# mach_sac_acquy.net
KiCad netlist of a schematic drawn in Altium Designer
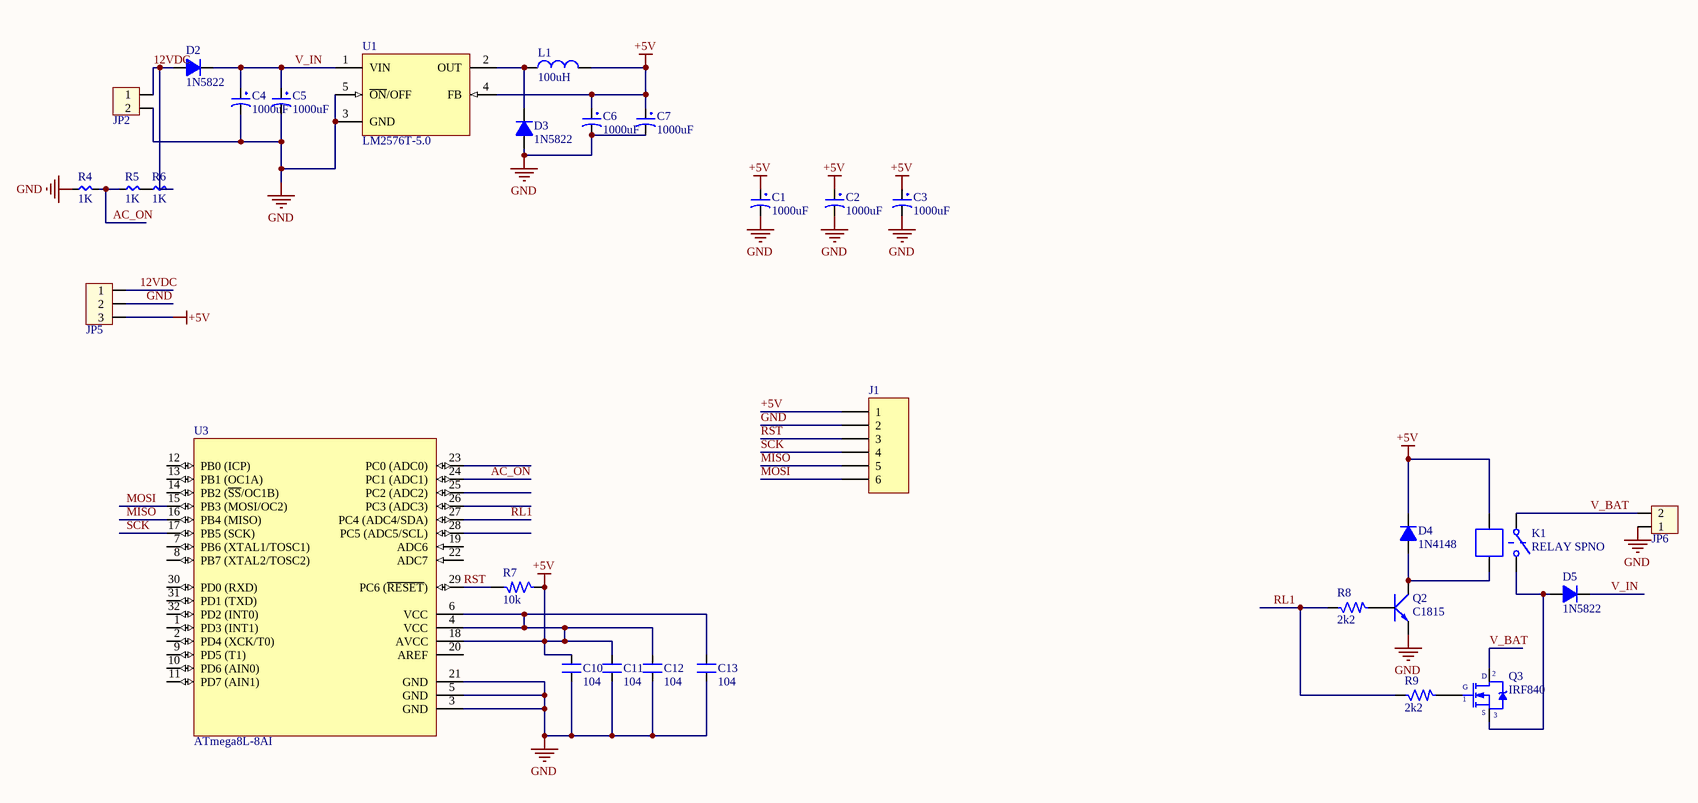
[diagram p0: mach_sac_acquy.SchDoc]

(export (version "E")
  (design (tool "Eeschema 10.0.6"))
  (components
    (comp (ref "C1")
      (value "1000uF")
      (footprint "CP1/2")
      (description "C 47uF/50V , 220uF/16V")
      (libsource (lib "Luyen_Schematics") (part "CP2"))
    )
    (comp (ref "C2")
      (value "1000uF")
      (footprint "CP1/2")
      (description "C 47uF/50V , 220uF/16V")
      (libsource (lib "Luyen_Schematics") (part "CP2"))
    )
    (comp (ref "C3")
      (value "1000uF")
      (footprint "CP1/2")
      (description "C 47uF/50V , 220uF/16V")
      (libsource (lib "Luyen_Schematics") (part "CP2"))
    )
    (comp (ref "C4")
      (value "1000uF")
      (footprint "CP2/4")
      (description "C 47uF/50V , 220uF/16V")
      (libsource (lib "Luyen_Schematics") (part "CP2"))
    )
    (comp (ref "C5")
      (value "1000uF")
      (footprint "CP2/4")
      (description "C 47uF/50V , 220uF/16V")
      (libsource (lib "Luyen_Schematics") (part "CP2"))
    )
    (comp (ref "C6")
      (value "1000uF")
      (footprint "CP2/4")
      (description "C 47uF/50V , 220uF/16V")
      (libsource (lib "Luyen_Schematics") (part "CP2"))
    )
    (comp (ref "C7")
      (value "1000uF")
      (footprint "CP2/4")
      (description "C 47uF/50V , 220uF/16V")
      (libsource (lib "Luyen_Schematics") (part "CP2"))
    )
    (comp (ref "C10")
      (value "104")
      (footprint "SM-0805")
      (description "Cap SMD")
      (libsource (lib "Luyen_Schematics") (part "CM"))
    )
    (comp (ref "C11")
      (value "104")
      (footprint "SM-0805")
      (description "Cap SMD")
      (libsource (lib "Luyen_Schematics") (part "CM"))
    )
    (comp (ref "C12")
      (value "104")
      (footprint "SM-0805")
      (description "Cap SMD")
      (libsource (lib "Luyen_Schematics") (part "CM"))
    )
    (comp (ref "C13")
      (value "104")
      (footprint "SM-0805")
      (description "Cap SMD")
      (libsource (lib "Luyen_Schematics") (part "CM"))
    )
    (comp (ref "D2")
      (value "1N5822")
      (footprint "D5A")
      (description "Diode 5A")
      (libsource (lib "Luyen_Schematics") (part "D5A"))
    )
    (comp (ref "D3")
      (value "1N5822")
      (footprint "D5A")
      (description "Diode 5A")
      (libsource (lib "Luyen_Schematics") (part "D5A"))
    )
    (comp (ref "D4")
      (value "1N4148")
      (footprint "1n4148 smd")
      (description "Diode 1A")
      (libsource (lib "Luyen_Schematics") (part "D1A"))
    )
    (comp (ref "D5")
      (value "1N5822")
      (footprint "D5A")
      (description "Diode 5A")
      (libsource (lib "Luyen_Schematics") (part "D5A"))
    )
    (comp (ref "J1")
      (value "Connector 5")
      (footprint "HDR1X6")
      (description "Header, 6-Pin")
      (fields (field (name "PUBLISHER") "Altium Limited"))
      (libsource (lib "Luyen_Schematics") (part "Header 6"))
    )
    (comp (ref "JP2")
      (value "Connector 2")
      (footprint "CON2")
      (libsource (lib "Luyen_Schematics") (part "CON2"))
    )
    (comp (ref "JP5")
      (value "Connector 3")
      (footprint "CON3")
      (libsource (lib "Luyen_Schematics") (part "CON3"))
    )
    (comp (ref "JP6") (value "Connector 2") (footprint "CON2") (libsource (lib "") (part "CON2_1")))
    (comp (ref "K1")
      (value "RELAY SPNO")
      (footprint "RELAY SONGCHUAN 834")
      (description "SINGLE Pole Dual-Throw Relay")
      (fields (field (name "PUBLISHER") "Altium Limited"))
      (libsource (lib "Luyen_Schematics") (part "RELAY SPNO"))
    )
    (comp (ref "L1")
      (value "100uH")
      (footprint "Inductor200")
      (description "Inductor")
      (libsource (lib "Luyen_Schematics") (part "Inductor"))
    )
    (comp (ref "Q2")
      (value "C1815")
      (footprint "SOT23B")
      (description "NPN 600mW, ECB")
      (libsource (lib "Luyen_Schematics") (part "C1815"))
    )
    (comp (ref "Q3")
      (value "IRF840")
      (footprint "QTO-220")
      (description "MOSFET N - CHANNEL 500V - 0.75 - 8A - TO-220")
      (libsource (lib "Luyen_Schematics") (part "IRF840"))
    )
    (comp (ref "R4")
      (value "1K")
      (footprint "SM-0805")
      (description "Resistor")
      (libsource (lib "THU VIEN CHAN") (part "RES 0805 BUT"))
    )
    (comp (ref "R5")
      (value "1K")
      (footprint "SM-0805")
      (description "Resistor")
      (libsource (lib "THU VIEN CHAN") (part "RES 0805 BUT"))
    )
    (comp (ref "R6")
      (value "1K")
      (footprint "SM-0805")
      (description "Resistor")
      (libsource (lib "THU VIEN CHAN") (part "RES 0805 BUT"))
    )
    (comp (ref "R7")
      (value "10k")
      (description "Resistor 1/4W")
      (libsource (lib "Luyen_Schematics") (part "R"))
    )
    (comp (ref "R8")
      (value "2k2")
      (description "Resistor 1/4W")
      (libsource (lib "Luyen_Schematics") (part "R"))
    )
    (comp (ref "R9")
      (value "2k2")
      (description "Resistor 1/4W")
      (libsource (lib "Luyen_Schematics") (part "R"))
    )
    (comp (ref "U1")
      (value "LM2576T-5.0")
      (description "SIMPLE SWITCHER; 3A Step-Down Voltage Regulator")
      (fields
        (field (name "MANUFACTURER") "National Semiconductor")
        (field (name "DIGIKEYPARTNUMBER") "LM2576T-5.0-ND")
        (field (name "PUBLISHER") "Altium Limited")
      )
      (libsource (lib "Luyen_Schematics") (part "LM2576T-5.0"))
    )
    (comp (ref "U3")
      (value "ATmega8L-8AI")
      (footprint "QFP7X7-G32/X.45N")
      (description "8-Bit AVR Microcontroller with 8K Bytes of In-System Programmable Flash Memory")
      (fields (field (name "PUBLISHER") "Altium Limited"))
      (libsource (lib "Atmel Microcontroller 8-Bit AVR") (part "ATmega8L-8AI"))
    )
  )
  (nets
    (net (code "1") (name "+5V") (class "Default")
      (node (ref "C1") (pin "1") (pinfunction "1_1") (pintype "passive"))
      (node (ref "C10") (pin "2") (pinfunction "2_2") (pintype "passive"))
      (node (ref "C11") (pin "2") (pinfunction "2_2") (pintype "passive"))
      (node (ref "C12") (pin "2") (pinfunction "2_2") (pintype "passive"))
      (node (ref "C13") (pin "2") (pinfunction "2_2") (pintype "passive"))
      (node (ref "C2") (pin "1") (pinfunction "1_1") (pintype "passive"))
      (node (ref "C3") (pin "1") (pinfunction "1_1") (pintype "passive"))
      (node (ref "C6") (pin "1") (pinfunction "1_1") (pintype "passive"))
      (node (ref "C7") (pin "1") (pinfunction "1_1") (pintype "passive"))
      (node (ref "D4") (pin "2") (pinfunction "K_2") (pintype "passive"))
      (node (ref "J1") (pin "1") (pinfunction "1_1") (pintype "passive"))
      (node (ref "JP5") (pin "3") (pinfunction "3_3") (pintype "passive"))
      (node (ref "K1") (pin "1") (pinfunction "1_1") (pintype "passive"))
      (node (ref "L1") (pin "2") (pinfunction "2_2") (pintype "passive"))
      (node (ref "R7") (pin "1") (pinfunction "1_1") (pintype "passive"))
      (node (ref "U1") (pin "4") (pinfunction "FB_4") (pintype "input"))
      (node (ref "U3") (pin "18") (pinfunction "AVCC_18") (pintype "power_in"))
      (node (ref "U3") (pin "4") (pinfunction "VCC_4") (pintype "power_in"))
      (node (ref "U3") (pin "6") (pinfunction "VCC_6") (pintype "power_in"))
    )
    (net (code "2") (name "/12VDC") (class "Default")
      (node (ref "D2") (pin "1") (pinfunction "A_1") (pintype "passive"))
      (node (ref "JP2") (pin "1") (pinfunction "1_1") (pintype "passive"))
      (node (ref "JP5") (pin "1") (pinfunction "1_1") (pintype "passive"))
      (node (ref "R6") (pin "1") (pinfunction "1_1") (pintype "passive"))
    )
    (net (code "3") (name "/AC_ON") (class "Default")
      (node (ref "R4") (pin "1") (pinfunction "1_1") (pintype "passive"))
      (node (ref "R5") (pin "2") (pinfunction "2_2") (pintype "passive"))
      (node (ref "U3") (pin "24") (pinfunction "PC1_(ADC1)_24") (pintype "bidirectional"))
    )
    (net (code "4") (name "/MISO") (class "Default")
      (node (ref "J1") (pin "5") (pinfunction "5_5") (pintype "passive"))
      (node (ref "U3") (pin "16") (pinfunction "PB4_(MISO)_16") (pintype "bidirectional"))
    )
    (net (code "5") (name "/MOSI") (class "Default")
      (node (ref "J1") (pin "6") (pinfunction "6_6") (pintype "passive"))
      (node (ref "U3") (pin "15") (pinfunction "PB3_(MOSI/OC2)_15") (pintype "bidirectional"))
    )
    (net (code "6") (name "/RL1") (class "Default")
      (node (ref "R8") (pin "1") (pinfunction "1_1") (pintype "passive"))
      (node (ref "R9") (pin "1") (pinfunction "1_1") (pintype "passive"))
      (node (ref "U3") (pin "27") (pinfunction "PC4_(ADC4/SDA)_27") (pintype "bidirectional"))
    )
    (net (code "7") (name "/RST") (class "Default")
      (node (ref "J1") (pin "3") (pinfunction "3_3") (pintype "passive"))
      (node (ref "R7") (pin "2") (pinfunction "2_2") (pintype "passive"))
      (node (ref "U3") (pin "29") (pinfunction "PC6_(~{RESET})_29") (pintype "bidirectional"))
    )
    (net (code "8") (name "/SCK") (class "Default")
      (node (ref "J1") (pin "4") (pinfunction "4_4") (pintype "passive"))
      (node (ref "U3") (pin "17") (pinfunction "PB5_(SCK)_17") (pintype "bidirectional"))
    )
    (net (code "9") (name "/V_BAT") (class "Default")
      (node (ref "JP6") (pin "2") (pinfunction "2_2") (pintype "passive"))
      (node (ref "K1") (pin "4") (pinfunction "4_4") (pintype "passive"))
      (node (ref "Q3") (pin "2") (pinfunction "D_2") (pintype "passive"))
    )
    (net (code "10") (name "/V_IN") (class "Default")
      (node (ref "C4") (pin "1") (pinfunction "1_1") (pintype "passive"))
      (node (ref "C5") (pin "1") (pinfunction "1_1") (pintype "passive"))
      (node (ref "D2") (pin "2") (pinfunction "K_2") (pintype "passive"))
      (node (ref "D5") (pin "2") (pinfunction "K_2") (pintype "passive"))
      (node (ref "U1") (pin "1") (pinfunction "VIN_1") (pintype "power_in"))
    )
    (net (code "11") (name "GND") (class "Default")
      (node (ref "C1") (pin "2") (pinfunction "2_2") (pintype "passive"))
      (node (ref "C10") (pin "1") (pinfunction "1_1") (pintype "passive"))
      (node (ref "C11") (pin "1") (pinfunction "1_1") (pintype "passive"))
      (node (ref "C12") (pin "1") (pinfunction "1_1") (pintype "passive"))
      (node (ref "C13") (pin "1") (pinfunction "1_1") (pintype "passive"))
      (node (ref "C2") (pin "2") (pinfunction "2_2") (pintype "passive"))
      (node (ref "C3") (pin "2") (pinfunction "2_2") (pintype "passive"))
      (node (ref "C4") (pin "2") (pinfunction "2_2") (pintype "passive"))
      (node (ref "C5") (pin "2") (pinfunction "2_2") (pintype "passive"))
      (node (ref "C6") (pin "2") (pinfunction "2_2") (pintype "passive"))
      (node (ref "C7") (pin "2") (pinfunction "2_2") (pintype "passive"))
      (node (ref "D3") (pin "1") (pinfunction "A_1") (pintype "passive"))
      (node (ref "J1") (pin "2") (pinfunction "2_2") (pintype "passive"))
      (node (ref "JP2") (pin "2") (pinfunction "2_2") (pintype "passive"))
      (node (ref "JP5") (pin "2") (pinfunction "2_2") (pintype "passive"))
      (node (ref "JP6") (pin "1") (pinfunction "1_1") (pintype "passive"))
      (node (ref "Q2") (pin "1") (pinfunction "E_1") (pintype "passive"))
      (node (ref "R4") (pin "2") (pinfunction "2_2") (pintype "passive"))
      (node (ref "U1") (pin "3") (pinfunction "GND_3") (pintype "power_in"))
      (node (ref "U1") (pin "5") (pinfunction "~{ON}/OFF_5") (pintype "input"))
      (node (ref "U3") (pin "21") (pinfunction "GND_21") (pintype "power_in"))
      (node (ref "U3") (pin "3") (pinfunction "GND_3") (pintype "power_in"))
      (node (ref "U3") (pin "5") (pinfunction "GND_5") (pintype "power_in"))
    )
    (net (code "12") (name "Net-(D3-K)") (class "Default")
      (node (ref "D3") (pin "2") (pinfunction "K_2") (pintype "passive"))
      (node (ref "L1") (pin "1") (pinfunction "1_1") (pintype "passive"))
      (node (ref "U1") (pin "2") (pinfunction "OUT_2") (pintype "power_in"))
    )
    (net (code "13") (name "Net-(D4-A)") (class "Default")
      (node (ref "D4") (pin "1") (pinfunction "A_1") (pintype "passive"))
      (node (ref "K1") (pin "2") (pinfunction "2_2") (pintype "passive"))
      (node (ref "Q2") (pin "2") (pinfunction "C_2") (pintype "passive"))
    )
    (net (code "14") (name "Net-(D5-A)") (class "Default")
      (node (ref "D5") (pin "1") (pinfunction "A_1") (pintype "passive"))
      (node (ref "K1") (pin "3") (pinfunction "3_3") (pintype "passive"))
      (node (ref "Q3") (pin "3") (pinfunction "S_3") (pintype "passive"))
    )
    (net (code "15") (name "Net-(Q2-B)") (class "Default")
      (node (ref "Q2") (pin "3") (pinfunction "B_3") (pintype "passive"))
      (node (ref "R8") (pin "2") (pinfunction "2_2") (pintype "passive"))
    )
    (net (code "16") (name "Net-(Q3-G)") (class "Default")
      (node (ref "Q3") (pin "1") (pinfunction "G_1") (pintype "passive"))
      (node (ref "R9") (pin "2") (pinfunction "2_2") (pintype "passive"))
    )
    (net (code "17") (name "Net-(R5-Pad1)") (class "Default")
      (node (ref "R5") (pin "1") (pinfunction "1_1") (pintype "passive"))
      (node (ref "R6") (pin "2") (pinfunction "2_2") (pintype "passive"))
    )
    (net (code "18") (name "unconnected-(U3-ADC6-Pad19)") (class "Default")
      (node (ref "U3") (pin "19") (pinfunction "ADC6_19") (pintype "input"))
    )
    (net (code "19") (name "unconnected-(U3-ADC7-Pad22)") (class "Default")
      (node (ref "U3") (pin "22") (pinfunction "ADC7_22") (pintype "input"))
    )
    (net (code "20") (name "unconnected-(U3-AREF-Pad20)") (class "Default")
      (node (ref "U3") (pin "20") (pinfunction "AREF_20") (pintype "passive"))
    )
    (net (code "21") (name "unconnected-(U3-PB0_(ICP)-Pad12)") (class "Default")
      (node (ref "U3") (pin "12") (pinfunction "PB0_(ICP)_12") (pintype "bidirectional"))
    )
    (net (code "22") (name "unconnected-(U3-PB1_(OC1A)-Pad13)") (class "Default")
      (node (ref "U3") (pin "13") (pinfunction "PB1_(OC1A)_13") (pintype "bidirectional"))
    )
    (net (code "23") (name "unconnected-(U3-PB2_(~{SS}{slash}OC1B)-Pad14)") (class "Default")
      (node (ref "U3") (pin "14") (pinfunction "PB2_(~{SS}/OC1B)_14") (pintype "bidirectional"))
    )
    (net (code "24") (name "unconnected-(U3-PB6_(XTAL1{slash}TOSC1)-Pad7)") (class "Default")
      (node (ref "U3") (pin "7") (pinfunction "PB6_(XTAL1/TOSC1)_7") (pintype "bidirectional"))
    )
    (net (code "25") (name "unconnected-(U3-PB7_(XTAL2{slash}TOSC2)-Pad8)") (class "Default")
      (node (ref "U3") (pin "8") (pinfunction "PB7_(XTAL2/TOSC2)_8") (pintype "bidirectional"))
    )
    (net (code "26") (name "unconnected-(U3-PC0_(ADC0)-Pad23)") (class "Default")
      (node (ref "U3") (pin "23") (pinfunction "PC0_(ADC0)_23") (pintype "bidirectional"))
    )
    (net (code "27") (name "unconnected-(U3-PC2_(ADC2)-Pad25)") (class "Default")
      (node (ref "U3") (pin "25") (pinfunction "PC2_(ADC2)_25") (pintype "bidirectional"))
    )
    (net (code "28") (name "unconnected-(U3-PC3_(ADC3)-Pad26)") (class "Default")
      (node (ref "U3") (pin "26") (pinfunction "PC3_(ADC3)_26") (pintype "bidirectional"))
    )
    (net (code "29") (name "unconnected-(U3-PC5_(ADC5{slash}SCL)-Pad28)") (class "Default")
      (node (ref "U3") (pin "28") (pinfunction "PC5_(ADC5/SCL)_28") (pintype "bidirectional"))
    )
    (net (code "30") (name "unconnected-(U3-PD0_(RXD)-Pad30)") (class "Default")
      (node (ref "U3") (pin "30") (pinfunction "PD0_(RXD)_30") (pintype "bidirectional"))
    )
    (net (code "31") (name "unconnected-(U3-PD1_(TXD)-Pad31)") (class "Default")
      (node (ref "U3") (pin "31") (pinfunction "PD1_(TXD)_31") (pintype "bidirectional"))
    )
    (net (code "32") (name "unconnected-(U3-PD2_(INT0)-Pad32)") (class "Default")
      (node (ref "U3") (pin "32") (pinfunction "PD2_(INT0)_32") (pintype "bidirectional"))
    )
    (net (code "33") (name "unconnected-(U3-PD3_(INT1)-Pad1)") (class "Default")
      (node (ref "U3") (pin "1") (pinfunction "PD3_(INT1)_1") (pintype "bidirectional"))
    )
    (net (code "34") (name "unconnected-(U3-PD4_(XCK{slash}T0)-Pad2)") (class "Default")
      (node (ref "U3") (pin "2") (pinfunction "PD4_(XCK/T0)_2") (pintype "bidirectional"))
    )
    (net (code "35") (name "unconnected-(U3-PD5_(T1)-Pad9)") (class "Default")
      (node (ref "U3") (pin "9") (pinfunction "PD5_(T1)_9") (pintype "bidirectional"))
    )
    (net (code "36") (name "unconnected-(U3-PD6_(AIN0)-Pad10)") (class "Default")
      (node (ref "U3") (pin "10") (pinfunction "PD6_(AIN0)_10") (pintype "bidirectional"))
    )
    (net (code "37") (name "unconnected-(U3-PD7_(AIN1)-Pad11)") (class "Default")
      (node (ref "U3") (pin "11") (pinfunction "PD7_(AIN1)_11") (pintype "bidirectional"))
    )
  )
)
